# ethernet-expansion.net
KiCad netlist of a schematic drawn in EAGLE
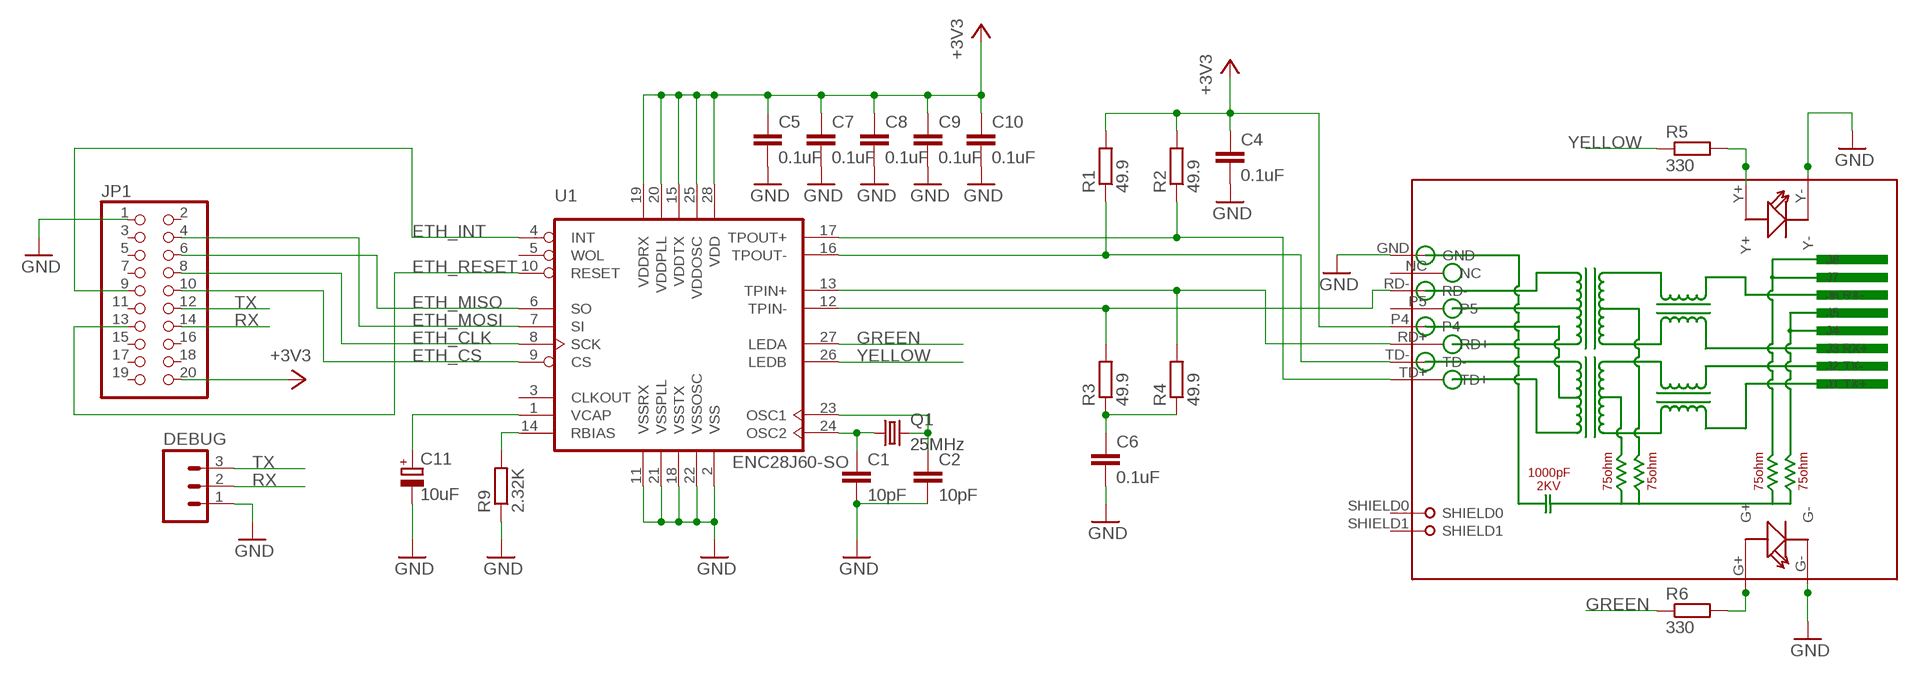
[diagram p0: schematic, sheet 1]

(export (version "E")
  (design (tool "Eeschema 10.0.6"))
  (components
    (comp (ref "C1")
      (value "10pF")
      (footprint "eagle-import:C0805")
      (libsource (lib "eagle-import") (part "C-EUC0805"))
    )
    (comp (ref "C2")
      (value "10pF")
      (footprint "eagle-import:C0805")
      (libsource (lib "eagle-import") (part "C-EUC0805"))
    )
    (comp (ref "C4")
      (value "0.1uF")
      (footprint "eagle-import:C0805")
      (libsource (lib "eagle-import") (part "C-EUC0805"))
    )
    (comp (ref "C5")
      (value "0.1uF")
      (footprint "eagle-import:C0805")
      (libsource (lib "eagle-import") (part "C-EUC0805"))
    )
    (comp (ref "C6")
      (value "0.1uF")
      (footprint "eagle-import:C0805")
      (libsource (lib "eagle-import") (part "C-EUC0805"))
    )
    (comp (ref "C7")
      (value "0.1uF")
      (footprint "eagle-import:C0805")
      (libsource (lib "eagle-import") (part "C-EUC0805"))
    )
    (comp (ref "C8")
      (value "0.1uF")
      (footprint "eagle-import:C0805")
      (libsource (lib "eagle-import") (part "C-EUC0805"))
    )
    (comp (ref "C9")
      (value "0.1uF")
      (footprint "eagle-import:C0805")
      (libsource (lib "eagle-import") (part "C-EUC0805"))
    )
    (comp (ref "C10")
      (value "0.1uF")
      (footprint "eagle-import:C0805")
      (libsource (lib "eagle-import") (part "C-EUC0805"))
    )
    (comp (ref "C11")
      (value "10uF")
      (footprint "eagle-import:E2-4")
      (libsource (lib "eagle-import") (part "CPOL-EUE2-4"))
    )
    (comp (ref "DEBUG")
      (value "M03PTH")
      (footprint "eagle-import:1X03")
      (libsource (lib "eagle-import") (part "M03PTH"))
    )
    (comp (ref "JP1")
      (value "PINHD-2X10")
      (footprint "eagle-import:2X10")
      (libsource (lib "eagle-import") (part "PINHD-2X10"))
    )
    (comp (ref "Q1")
      (value "25MHz")
      (footprint "eagle-import:HC49_S")
      (libsource (lib "eagle-import") (part "CRYSTALHC49S"))
    )
    (comp (ref "R1")
      (value "49.9")
      (footprint "eagle-import:M0805")
      (libsource (lib "eagle-import") (part "R-EU_M0805"))
    )
    (comp (ref "R2")
      (value "49.9")
      (footprint "eagle-import:M0805")
      (libsource (lib "eagle-import") (part "R-EU_M0805"))
    )
    (comp (ref "R3")
      (value "49.9")
      (footprint "eagle-import:M0805")
      (libsource (lib "eagle-import") (part "R-EU_M0805"))
    )
    (comp (ref "R4")
      (value "49.9")
      (footprint "eagle-import:M0805")
      (libsource (lib "eagle-import") (part "R-EU_M0805"))
    )
    (comp (ref "R5")
      (value "330")
      (footprint "eagle-import:M0805")
      (libsource (lib "eagle-import") (part "R-EU_M0805"))
    )
    (comp (ref "R6")
      (value "330")
      (footprint "eagle-import:M0805")
      (libsource (lib "eagle-import") (part "R-EU_M0805"))
    )
    (comp (ref "R9")
      (value "2.32K")
      (footprint "eagle-import:M0805")
      (libsource (lib "eagle-import") (part "R-EU_M0805"))
    )
    (comp (ref "RJ1")
      (value "HR911105A")
      (footprint "eagle-import:HR911105A")
      (libsource (lib "eagle-import") (part "HR911105A"))
    )
    (comp (ref "U1")
      (value "ENC28J60-SO")
      (footprint "eagle-import:SO28W")
      (libsource (lib "eagle-import") (part "ENC28J60-SO"))
    )
  )
  (nets
    (net (code "1") (name "+3V3") (class "Default")
      (node (ref "C10") (pin "1") (pinfunction "1_1") (pintype "passive"))
      (node (ref "C4") (pin "1") (pinfunction "1_1") (pintype "passive"))
      (node (ref "C5") (pin "1") (pinfunction "1_1") (pintype "passive"))
      (node (ref "C7") (pin "1") (pinfunction "1_1") (pintype "passive"))
      (node (ref "C8") (pin "1") (pinfunction "1_1") (pintype "passive"))
      (node (ref "C9") (pin "1") (pinfunction "1_1") (pintype "passive"))
      (node (ref "JP1") (pin "20") (pinfunction "20_20") (pintype "passive"))
      (node (ref "R1") (pin "2") (pinfunction "2_2") (pintype "passive"))
      (node (ref "R2") (pin "2") (pinfunction "2_2") (pintype "passive"))
      (node (ref "RJ1") (pin "P4") (pinfunction "P4_P4") (pintype "bidirectional"))
      (node (ref "U1") (pin "15") (pinfunction "VDDTX_15") (pintype "power_in"))
      (node (ref "U1") (pin "19") (pinfunction "VDDRX_19") (pintype "power_in"))
      (node (ref "U1") (pin "20") (pinfunction "VDDPLL_20") (pintype "power_in"))
      (node (ref "U1") (pin "25") (pinfunction "VDDOSC_25") (pintype "power_in"))
      (node (ref "U1") (pin "28") (pinfunction "VDD_28") (pintype "power_in"))
    )
    (net (code "2") (name "/ETH_CLK") (class "Default")
      (node (ref "JP1") (pin "8") (pinfunction "8_8") (pintype "passive"))
      (node (ref "U1") (pin "8") (pinfunction "SCK_8") (pintype "input"))
    )
    (net (code "3") (name "/ETH_CS") (class "Default")
      (node (ref "JP1") (pin "10") (pinfunction "10_10") (pintype "passive"))
      (node (ref "U1") (pin "9") (pinfunction "CS_9") (pintype "input"))
    )
    (net (code "4") (name "/ETH_INT") (class "Default")
      (node (ref "JP1") (pin "9") (pinfunction "9_9") (pintype "passive"))
      (node (ref "U1") (pin "4") (pinfunction "INT_4") (pintype "output"))
    )
    (net (code "5") (name "/ETH_MISO") (class "Default")
      (node (ref "JP1") (pin "6") (pinfunction "6_6") (pintype "passive"))
      (node (ref "U1") (pin "6") (pinfunction "SO_6") (pintype "output"))
    )
    (net (code "6") (name "/ETH_MOSI") (class "Default")
      (node (ref "JP1") (pin "4") (pinfunction "4_4") (pintype "passive"))
      (node (ref "U1") (pin "7") (pinfunction "SI_7") (pintype "input"))
    )
    (net (code "7") (name "/ETH_RESET") (class "Default")
      (node (ref "JP1") (pin "13") (pinfunction "13_13") (pintype "passive"))
      (node (ref "U1") (pin "10") (pinfunction "RESET_10") (pintype "input"))
    )
    (net (code "8") (name "/GREEN") (class "Default")
      (node (ref "R6") (pin "1") (pinfunction "1_1") (pintype "passive"))
      (node (ref "U1") (pin "27") (pinfunction "LEDA_27") (pintype "output"))
    )
    (net (code "9") (name "/RX") (class "Default")
      (node (ref "DEBUG") (pin "2") (pinfunction "2_2") (pintype "passive"))
      (node (ref "JP1") (pin "14") (pinfunction "14_14") (pintype "passive"))
    )
    (net (code "10") (name "/TX") (class "Default")
      (node (ref "DEBUG") (pin "3") (pinfunction "3_3") (pintype "passive"))
      (node (ref "JP1") (pin "12") (pinfunction "12_12") (pintype "passive"))
    )
    (net (code "11") (name "/YELLOW") (class "Default")
      (node (ref "R5") (pin "1") (pinfunction "1_1") (pintype "passive"))
      (node (ref "U1") (pin "26") (pinfunction "LEDB_26") (pintype "output"))
    )
    (net (code "12") (name "GND") (class "Default")
      (node (ref "C1") (pin "2") (pinfunction "2_2") (pintype "passive"))
      (node (ref "C10") (pin "2") (pinfunction "2_2") (pintype "passive"))
      (node (ref "C11") (pin "-") (pinfunction "-_-") (pintype "passive"))
      (node (ref "C2") (pin "2") (pinfunction "2_2") (pintype "passive"))
      (node (ref "C4") (pin "2") (pinfunction "2_2") (pintype "passive"))
      (node (ref "C5") (pin "2") (pinfunction "2_2") (pintype "passive"))
      (node (ref "C6") (pin "2") (pinfunction "2_2") (pintype "passive"))
      (node (ref "C7") (pin "2") (pinfunction "2_2") (pintype "passive"))
      (node (ref "C8") (pin "2") (pinfunction "2_2") (pintype "passive"))
      (node (ref "C9") (pin "2") (pinfunction "2_2") (pintype "passive"))
      (node (ref "DEBUG") (pin "1") (pinfunction "1_1") (pintype "passive"))
      (node (ref "JP1") (pin "1") (pinfunction "1_1") (pintype "passive"))
      (node (ref "R9") (pin "1") (pinfunction "1_1") (pintype "passive"))
      (node (ref "RJ1") (pin "G-") (pinfunction "G-_G-") (pintype "bidirectional"))
      (node (ref "RJ1") (pin "GND") (pinfunction "GND_GND") (pintype "bidirectional"))
      (node (ref "RJ1") (pin "Y-") (pinfunction "Y-_Y-") (pintype "bidirectional"))
      (node (ref "U1") (pin "11") (pinfunction "VSSRX_11") (pintype "power_in"))
      (node (ref "U1") (pin "18") (pinfunction "VSSTX_18") (pintype "power_in"))
      (node (ref "U1") (pin "2") (pinfunction "VSS_2") (pintype "power_in"))
      (node (ref "U1") (pin "21") (pinfunction "VSSPLL_21") (pintype "power_in"))
      (node (ref "U1") (pin "22") (pinfunction "VSSOSC_22") (pintype "power_in"))
    )
    (net (code "13") (name "Net-(C6-Pad1)") (class "Default")
      (node (ref "C6") (pin "1") (pinfunction "1_1") (pintype "passive"))
      (node (ref "R3") (pin "1") (pinfunction "1_1") (pintype "passive"))
      (node (ref "R4") (pin "1") (pinfunction "1_1") (pintype "passive"))
    )
    (net (code "14") (name "Net-(R5-Pad2)") (class "Default")
      (node (ref "R5") (pin "2") (pinfunction "2_2") (pintype "passive"))
      (node (ref "RJ1") (pin "Y+") (pinfunction "Y+_Y+") (pintype "bidirectional"))
    )
    (net (code "15") (name "Net-(R6-Pad2)") (class "Default")
      (node (ref "R6") (pin "2") (pinfunction "2_2") (pintype "passive"))
      (node (ref "RJ1") (pin "G+") (pinfunction "G+_G+") (pintype "bidirectional"))
    )
    (net (code "16") (name "Net-(U1-OSC1)") (class "Default")
      (node (ref "C2") (pin "1") (pinfunction "1_1") (pintype "passive"))
      (node (ref "Q1") (pin "2") (pinfunction "2_2") (pintype "passive"))
      (node (ref "U1") (pin "23") (pinfunction "OSC1_23") (pintype "input"))
    )
    (net (code "17") (name "Net-(U1-OSC2)") (class "Default")
      (node (ref "C1") (pin "1") (pinfunction "1_1") (pintype "passive"))
      (node (ref "Q1") (pin "1") (pinfunction "1_1") (pintype "passive"))
      (node (ref "U1") (pin "24") (pinfunction "OSC2_24") (pintype "output"))
    )
    (net (code "18") (name "Net-(U1-RBIAS)") (class "Default")
      (node (ref "R9") (pin "2") (pinfunction "2_2") (pintype "passive"))
      (node (ref "U1") (pin "14") (pinfunction "RBIAS_14") (pintype "passive"))
    )
    (net (code "19") (name "Net-(U1-TPIN+)") (class "Default")
      (node (ref "R4") (pin "2") (pinfunction "2_2") (pintype "passive"))
      (node (ref "RJ1") (pin "RD+") (pinfunction "RD+_RD+") (pintype "bidirectional"))
      (node (ref "U1") (pin "13") (pinfunction "TPIN+_13") (pintype "input"))
    )
    (net (code "20") (name "Net-(U1-TPIN-)") (class "Default")
      (node (ref "R3") (pin "2") (pinfunction "2_2") (pintype "passive"))
      (node (ref "RJ1") (pin "RD-") (pinfunction "RD-_RD-") (pintype "bidirectional"))
      (node (ref "U1") (pin "12") (pinfunction "TPIN-_12") (pintype "input"))
    )
    (net (code "21") (name "Net-(U1-TPOUT+)") (class "Default")
      (node (ref "R2") (pin "1") (pinfunction "1_1") (pintype "passive"))
      (node (ref "RJ1") (pin "TD+") (pinfunction "TD+_TD+") (pintype "bidirectional"))
      (node (ref "U1") (pin "17") (pinfunction "TPOUT+_17") (pintype "output"))
    )
    (net (code "22") (name "Net-(U1-TPOUT-)") (class "Default")
      (node (ref "R1") (pin "1") (pinfunction "1_1") (pintype "passive"))
      (node (ref "RJ1") (pin "TD-") (pinfunction "TD-_TD-") (pintype "bidirectional"))
      (node (ref "U1") (pin "16") (pinfunction "TPOUT-_16") (pintype "output"))
    )
    (net (code "23") (name "Net-(U1-VCAP)") (class "Default")
      (node (ref "C11") (pin "+") (pinfunction "+_+") (pintype "passive"))
      (node (ref "U1") (pin "1") (pinfunction "VCAP_1") (pintype "power_in"))
    )
    (net (code "24") (name "unconnected-(JP1-Pad2)") (class "Default")
      (node (ref "JP1") (pin "2") (pinfunction "2_2") (pintype "passive"))
    )
    (net (code "25") (name "unconnected-(JP1-Pad3)") (class "Default")
      (node (ref "JP1") (pin "3") (pinfunction "3_3") (pintype "passive"))
    )
    (net (code "26") (name "unconnected-(JP1-Pad5)") (class "Default")
      (node (ref "JP1") (pin "5") (pinfunction "5_5") (pintype "passive"))
    )
    (net (code "27") (name "unconnected-(JP1-Pad7)") (class "Default")
      (node (ref "JP1") (pin "7") (pinfunction "7_7") (pintype "passive"))
    )
    (net (code "28") (name "unconnected-(JP1-Pad11)") (class "Default")
      (node (ref "JP1") (pin "11") (pinfunction "11_11") (pintype "passive"))
    )
    (net (code "29") (name "unconnected-(JP1-Pad15)") (class "Default")
      (node (ref "JP1") (pin "15") (pinfunction "15_15") (pintype "passive"))
    )
    (net (code "30") (name "unconnected-(JP1-Pad16)") (class "Default")
      (node (ref "JP1") (pin "16") (pinfunction "16_16") (pintype "passive"))
    )
    (net (code "31") (name "unconnected-(JP1-Pad17)") (class "Default")
      (node (ref "JP1") (pin "17") (pinfunction "17_17") (pintype "passive"))
    )
    (net (code "32") (name "unconnected-(JP1-Pad18)") (class "Default")
      (node (ref "JP1") (pin "18") (pinfunction "18_18") (pintype "passive"))
    )
    (net (code "33") (name "unconnected-(JP1-Pad19)") (class "Default")
      (node (ref "JP1") (pin "19") (pinfunction "19_19") (pintype "passive"))
    )
    (net (code "34") (name "unconnected-(RJ1-PadNC)") (class "Default")
      (node (ref "RJ1") (pin "NC") (pinfunction "NC_NC") (pintype "bidirectional"))
    )
    (net (code "35") (name "unconnected-(RJ1-PadP5)") (class "Default")
      (node (ref "RJ1") (pin "P5") (pinfunction "P5_P5") (pintype "bidirectional"))
    )
    (net (code "36") (name "unconnected-(RJ1-PadSHIELD0)") (class "Default")
      (node (ref "RJ1") (pin "SHIELD0") (pinfunction "SHIELD0_SHIELD0") (pintype "bidirectional"))
    )
    (net (code "37") (name "unconnected-(RJ1-PadSHIELD1)") (class "Default")
      (node (ref "RJ1") (pin "SHIELD1") (pinfunction "SHIELD1_SHIELD1") (pintype "bidirectional"))
    )
    (net (code "38") (name "unconnected-(U1-CLKOUT-Pad3)") (class "Default")
      (node (ref "U1") (pin "3") (pinfunction "CLKOUT_3") (pintype "output"))
    )
    (net (code "39") (name "unconnected-(U1-WOL-Pad5)") (class "Default")
      (node (ref "U1") (pin "5") (pinfunction "WOL_5") (pintype "output"))
    )
  )
)
